# PS2Kbd.net
KiCad netlist of a schematic drawn in EAGLE
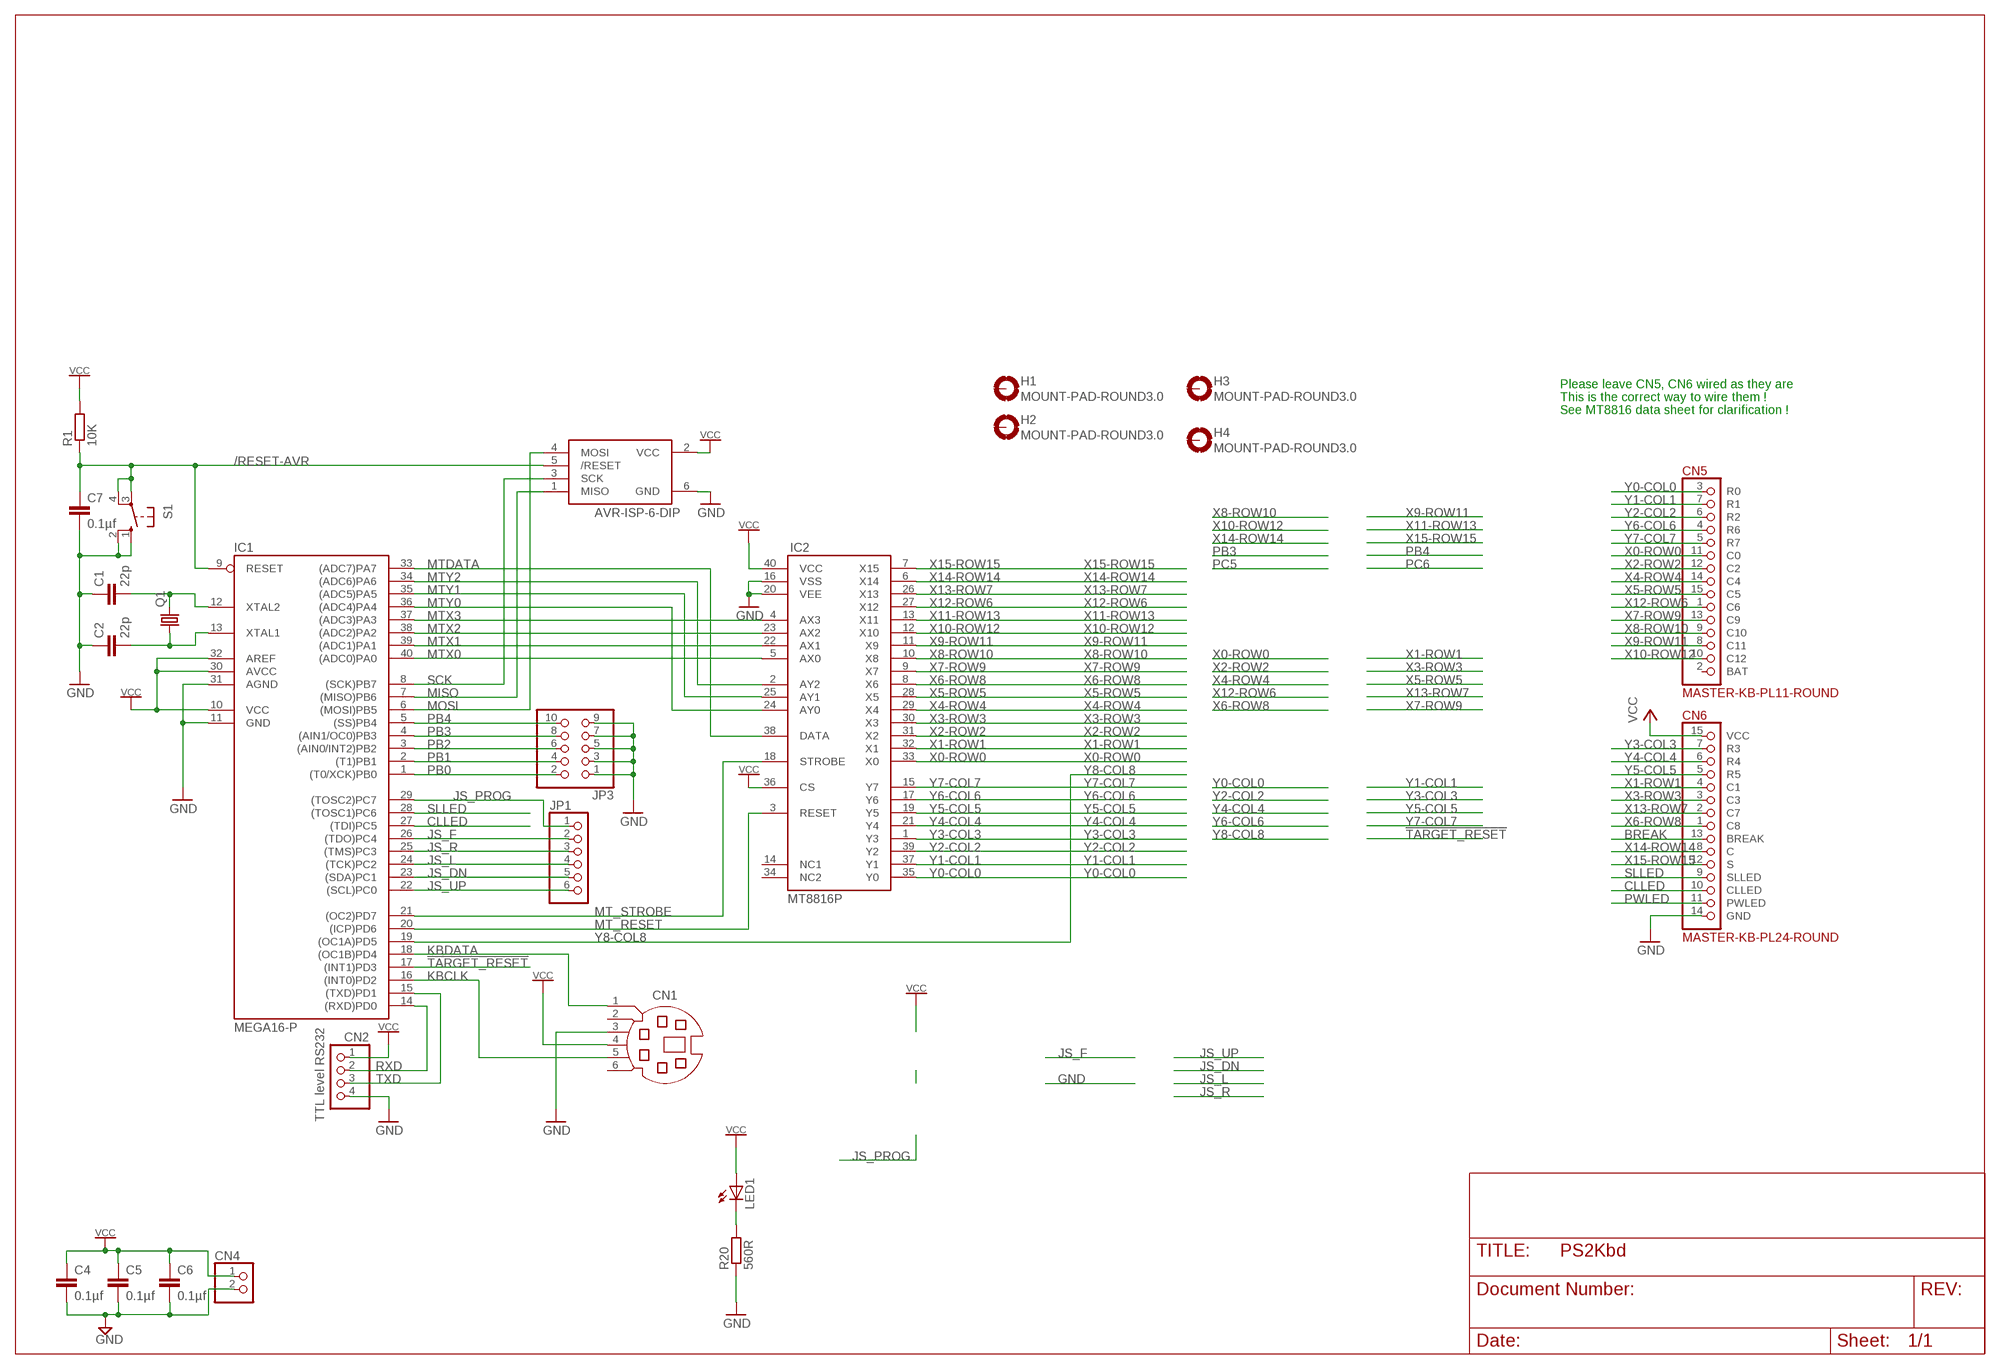
[diagram p0: schematic, sheet 1]

(export (version "E")
  (design (tool "Eeschema 10.0.6"))
  (components
    (comp (ref "C1")
      (value "22p")
      (footprint "eagle-import:C025-025X050")
      (libsource (lib "eagle-import") (part "C-EU025-025X050"))
    )
    (comp (ref "C2")
      (value "22p")
      (footprint "eagle-import:C025-025X050")
      (libsource (lib "eagle-import") (part "C-EU025-025X050"))
    )
    (comp (ref "C4")
      (value "0.1µf")
      (footprint "eagle-import:C025-025X050")
      (libsource (lib "eagle-import") (part "C-EU025-025X050"))
    )
    (comp (ref "C5")
      (value "0.1µf")
      (footprint "eagle-import:C025-025X050")
      (libsource (lib "eagle-import") (part "C-EU025-025X050"))
    )
    (comp (ref "C6")
      (value "0.1µf")
      (footprint "eagle-import:C025-025X050")
      (libsource (lib "eagle-import") (part "C-EU025-025X050"))
    )
    (comp (ref "C7")
      (value "0.1µf")
      (footprint "eagle-import:C025-025X050")
      (libsource (lib "eagle-import") (part "C-EU025-025X050"))
    )
    (comp (ref "CN1")
      (value "MD06SS")
      (footprint "eagle-import:MDIN06SS")
      (libsource (lib "eagle-import") (part "MD06SS"))
    )
    (comp (ref "CN2")
      (value "PINHD-1X4")
      (footprint "eagle-import:1X04")
      (libsource (lib "eagle-import") (part "PINHD-1X4"))
    )
    (comp (ref "CN3")
      (value "AVR-ISP-6-DIP")
      (footprint "eagle-import:2X3")
      (libsource (lib "eagle-import") (part "AVR-ISP-6-DIP"))
    )
    (comp (ref "CN4")
      (value "PINHD-1X2")
      (footprint "eagle-import:1X02")
      (libsource (lib "eagle-import") (part "PINHD-1X2"))
    )
    (comp (ref "CN5")
      (value "MASTER-KB-PL11-ROUND")
      (footprint "eagle-import:1X15-ROUND")
      (libsource (lib "eagle-import") (part "MASTER-KB-PL11-ROUND"))
    )
    (comp (ref "CN6")
      (value "MASTER-KB-PL24-ROUND")
      (footprint "eagle-import:1X15-ROUND")
      (libsource (lib "eagle-import") (part "MASTER-KB-PL24-ROUND"))
    )
    (comp (ref "H1")
      (value "MOUNT-PAD-ROUND3.0")
      (footprint "eagle-import:3,0-PAD")
      (libsource (lib "eagle-import") (part "MOUNT-PAD-ROUND3.0"))
    )
    (comp (ref "H2")
      (value "MOUNT-PAD-ROUND3.0")
      (footprint "eagle-import:3,0-PAD")
      (libsource (lib "eagle-import") (part "MOUNT-PAD-ROUND3.0"))
    )
    (comp (ref "H3")
      (value "MOUNT-PAD-ROUND3.0")
      (footprint "eagle-import:3,0-PAD")
      (libsource (lib "eagle-import") (part "MOUNT-PAD-ROUND3.0"))
    )
    (comp (ref "H4")
      (value "MOUNT-PAD-ROUND3.0")
      (footprint "eagle-import:3,0-PAD")
      (libsource (lib "eagle-import") (part "MOUNT-PAD-ROUND3.0"))
    )
    (comp (ref "IC1")
      (value "MEGA16-P")
      (footprint "eagle-import:DIL40")
      (libsource (lib "eagle-import") (part "MEGA16-P"))
    )
    (comp (ref "IC2")
      (value "MT8816P")
      (footprint "eagle-import:DIL40")
      (libsource (lib "eagle-import") (part "MT8816P"))
    )
    (comp (ref "JP1")
      (value "PINHD-1X6")
      (footprint "eagle-import:1X06")
      (libsource (lib "eagle-import") (part "PINHD-1X6"))
    )
    (comp (ref "JP3")
      (value "PINHD-2X5")
      (footprint "eagle-import:2X05")
      (libsource (lib "eagle-import") (part "PINHD-2X5"))
    )
    (comp (ref "LED1")
      (value "LED3MM")
      (footprint "eagle-import:LED3MM")
      (libsource (lib "eagle-import") (part "LED3MM"))
    )
    (comp (ref "Q1")
      (value "CRYSTALHC49S")
      (footprint "eagle-import:HC49_S")
      (libsource (lib "eagle-import") (part "CRYSTALHC49S"))
    )
    (comp (ref "R1")
      (value "10K")
      (footprint "eagle-import:0207_10")
      (libsource (lib "eagle-import") (part "R-EU_0207/10"))
    )
    (comp (ref "R20")
      (value "560R")
      (footprint "eagle-import:0207_10")
      (libsource (lib "eagle-import") (part "R-EU_0207/10"))
    )
    (comp (ref "S1")
      (value "10-XX")
      (footprint "eagle-import:B3F-10XX")
      (fields (field (name "MPN") "B3F-1000"))
      (libsource (lib "eagle-import") (part "10-XX"))
    )
  )
  (nets
    (net (code "1") (name "/BREAK") (class "Default")
      (node (ref "CN6") (pin "13") (pinfunction "BREAK_13") (pintype "passive"))
    )
    (net (code "2") (name "/CLLED") (class "Default")
      (node (ref "CN6") (pin "10") (pinfunction "CLLED_10") (pintype "passive"))
      (node (ref "IC1") (pin "27") (pinfunction "(TDI)PC5_27") (pintype "bidirectional"))
    )
    (net (code "3") (name "/JS_DN") (class "Default")
      (node (ref "IC1") (pin "23") (pinfunction "(SDA)PC1_23") (pintype "bidirectional"))
      (node (ref "JP1") (pin "5") (pinfunction "5_5") (pintype "passive"))
    )
    (net (code "4") (name "/JS_F") (class "Default")
      (node (ref "IC1") (pin "26") (pinfunction "(TDO)PC4_26") (pintype "bidirectional"))
      (node (ref "JP1") (pin "2") (pinfunction "2_2") (pintype "passive"))
    )
    (net (code "5") (name "/JS_L") (class "Default")
      (node (ref "IC1") (pin "24") (pinfunction "(TCK)PC2_24") (pintype "bidirectional"))
      (node (ref "JP1") (pin "4") (pinfunction "4_4") (pintype "passive"))
    )
    (net (code "6") (name "/JS_PROG") (class "Default")
      (node (ref "IC1") (pin "29") (pinfunction "(TOSC2)PC7_29") (pintype "bidirectional"))
      (node (ref "JP1") (pin "1") (pinfunction "1_1") (pintype "passive"))
    )
    (net (code "7") (name "/JS_R") (class "Default")
      (node (ref "IC1") (pin "25") (pinfunction "(TMS)PC3_25") (pintype "bidirectional"))
      (node (ref "JP1") (pin "3") (pinfunction "3_3") (pintype "passive"))
    )
    (net (code "8") (name "/JS_UP") (class "Default")
      (node (ref "IC1") (pin "22") (pinfunction "(SCL)PC0_22") (pintype "bidirectional"))
      (node (ref "JP1") (pin "6") (pinfunction "6_6") (pintype "passive"))
    )
    (net (code "9") (name "/KBCLK") (class "Default")
      (node (ref "CN1") (pin "5") (pinfunction "5_5") (pintype "passive"))
      (node (ref "IC1") (pin "16") (pinfunction "(INT0)PD2_16") (pintype "bidirectional"))
    )
    (net (code "10") (name "/KBDATA") (class "Default")
      (node (ref "CN1") (pin "1") (pinfunction "1_1") (pintype "passive"))
      (node (ref "IC1") (pin "18") (pinfunction "(OC1B)PD4_18") (pintype "bidirectional"))
    )
    (net (code "11") (name "/MISO") (class "Default")
      (node (ref "CN3") (pin "1") (pinfunction "MISO_1") (pintype "bidirectional"))
      (node (ref "IC1") (pin "7") (pinfunction "(MISO)PB6_7") (pintype "bidirectional"))
    )
    (net (code "12") (name "/MOSI") (class "Default")
      (node (ref "CN3") (pin "4") (pinfunction "MOSI_4") (pintype "bidirectional"))
      (node (ref "IC1") (pin "6") (pinfunction "(MOSI)PB5_6") (pintype "bidirectional"))
    )
    (net (code "13") (name "/MTDATA") (class "Default")
      (node (ref "IC1") (pin "33") (pinfunction "(ADC7)PA7_33") (pintype "bidirectional"))
      (node (ref "IC2") (pin "38") (pinfunction "DATA_38") (pintype "input"))
    )
    (net (code "14") (name "/MTX0") (class "Default")
      (node (ref "IC1") (pin "40") (pinfunction "(ADC0)PA0_40") (pintype "bidirectional"))
      (node (ref "IC2") (pin "5") (pinfunction "AX0_5") (pintype "input"))
    )
    (net (code "15") (name "/MTX1") (class "Default")
      (node (ref "IC1") (pin "39") (pinfunction "(ADC1)PA1_39") (pintype "bidirectional"))
      (node (ref "IC2") (pin "22") (pinfunction "AX1_22") (pintype "input"))
    )
    (net (code "16") (name "/MTX2") (class "Default")
      (node (ref "IC1") (pin "38") (pinfunction "(ADC2)PA2_38") (pintype "bidirectional"))
      (node (ref "IC2") (pin "23") (pinfunction "AX2_23") (pintype "input"))
    )
    (net (code "17") (name "/MTX3") (class "Default")
      (node (ref "IC1") (pin "37") (pinfunction "(ADC3)PA3_37") (pintype "bidirectional"))
      (node (ref "IC2") (pin "4") (pinfunction "AX3_4") (pintype "input"))
    )
    (net (code "18") (name "/MTY0") (class "Default")
      (node (ref "IC1") (pin "36") (pinfunction "(ADC4)PA4_36") (pintype "bidirectional"))
      (node (ref "IC2") (pin "24") (pinfunction "AY0_24") (pintype "input"))
    )
    (net (code "19") (name "/MTY1") (class "Default")
      (node (ref "IC1") (pin "35") (pinfunction "(ADC5)PA5_35") (pintype "bidirectional"))
      (node (ref "IC2") (pin "25") (pinfunction "AY1_25") (pintype "input"))
    )
    (net (code "20") (name "/MTY2") (class "Default")
      (node (ref "IC1") (pin "34") (pinfunction "(ADC6)PA6_34") (pintype "bidirectional"))
      (node (ref "IC2") (pin "2") (pinfunction "AY2_2") (pintype "input"))
    )
    (net (code "21") (name "/MT_RESET") (class "Default")
      (node (ref "IC1") (pin "20") (pinfunction "(ICP)PD6_20") (pintype "bidirectional"))
      (node (ref "IC2") (pin "3") (pinfunction "RESET_3") (pintype "input"))
    )
    (net (code "22") (name "/MT_STROBE") (class "Default")
      (node (ref "IC1") (pin "21") (pinfunction "(OC2)PD7_21") (pintype "bidirectional"))
      (node (ref "IC2") (pin "18") (pinfunction "STROBE_18") (pintype "input"))
    )
    (net (code "23") (name "/PB0") (class "Default")
      (node (ref "IC1") (pin "1") (pinfunction "(T0/XCK)PB0_1") (pintype "bidirectional"))
      (node (ref "JP3") (pin "2") (pinfunction "2_2") (pintype "passive"))
    )
    (net (code "24") (name "/PB1") (class "Default")
      (node (ref "IC1") (pin "2") (pinfunction "(T1)PB1_2") (pintype "bidirectional"))
      (node (ref "JP3") (pin "4") (pinfunction "4_4") (pintype "passive"))
    )
    (net (code "25") (name "/PB2") (class "Default")
      (node (ref "IC1") (pin "3") (pinfunction "(AIN0/INT2)PB2_3") (pintype "bidirectional"))
      (node (ref "JP3") (pin "6") (pinfunction "6_6") (pintype "passive"))
    )
    (net (code "26") (name "/PB3") (class "Default")
      (node (ref "IC1") (pin "4") (pinfunction "(AIN1/OC0)PB3_4") (pintype "bidirectional"))
      (node (ref "JP3") (pin "8") (pinfunction "8_8") (pintype "passive"))
    )
    (net (code "27") (name "/PB4") (class "Default")
      (node (ref "IC1") (pin "5") (pinfunction "(SS)PB4_5") (pintype "bidirectional"))
      (node (ref "JP3") (pin "10") (pinfunction "10_10") (pintype "passive"))
    )
    (net (code "30") (name "/PWLED") (class "Default")
      (node (ref "CN6") (pin "11") (pinfunction "PWLED_11") (pintype "passive"))
    )
    (net (code "31") (name "/RXD") (class "Default")
      (node (ref "CN2") (pin "2") (pinfunction "2_2") (pintype "passive"))
      (node (ref "IC1") (pin "14") (pinfunction "(RXD)PD0_14") (pintype "bidirectional"))
    )
    (net (code "32") (name "/SCK") (class "Default")
      (node (ref "CN3") (pin "3") (pinfunction "SCK_3") (pintype "bidirectional"))
      (node (ref "IC1") (pin "8") (pinfunction "(SCK)PB7_8") (pintype "bidirectional"))
    )
    (net (code "33") (name "/SLLED") (class "Default")
      (node (ref "CN6") (pin "9") (pinfunction "SLLED_9") (pintype "passive"))
      (node (ref "IC1") (pin "28") (pinfunction "(TOSC1)PC6_28") (pintype "bidirectional"))
    )
    (net (code "34") (name "/TXD") (class "Default")
      (node (ref "CN2") (pin "3") (pinfunction "3_3") (pintype "passive"))
      (node (ref "IC1") (pin "15") (pinfunction "(TXD)PD1_15") (pintype "bidirectional"))
    )
    (net (code "35") (name "/X0-ROW0") (class "Default")
      (node (ref "CN5") (pin "11") (pinfunction "C0_11") (pintype "passive"))
      (node (ref "IC2") (pin "33") (pinfunction "X0_33") (pintype "bidirectional"))
    )
    (net (code "36") (name "/X1-ROW1") (class "Default")
      (node (ref "CN6") (pin "4") (pinfunction "C1_4") (pintype "passive"))
      (node (ref "IC2") (pin "32") (pinfunction "X1_32") (pintype "bidirectional"))
    )
    (net (code "37") (name "/X2-ROW2") (class "Default")
      (node (ref "CN5") (pin "12") (pinfunction "C2_12") (pintype "passive"))
      (node (ref "IC2") (pin "31") (pinfunction "X2_31") (pintype "bidirectional"))
    )
    (net (code "38") (name "/X3-ROW3") (class "Default")
      (node (ref "CN6") (pin "3") (pinfunction "C3_3") (pintype "passive"))
      (node (ref "IC2") (pin "30") (pinfunction "X3_30") (pintype "bidirectional"))
    )
    (net (code "39") (name "/X4-ROW4") (class "Default")
      (node (ref "CN5") (pin "14") (pinfunction "C4_14") (pintype "passive"))
      (node (ref "IC2") (pin "29") (pinfunction "X4_29") (pintype "bidirectional"))
    )
    (net (code "40") (name "/X5-ROW5") (class "Default")
      (node (ref "CN5") (pin "15") (pinfunction "C5_15") (pintype "passive"))
      (node (ref "IC2") (pin "28") (pinfunction "X5_28") (pintype "bidirectional"))
    )
    (net (code "41") (name "/X6-ROW8") (class "Default")
      (node (ref "CN6") (pin "1") (pinfunction "C8_1") (pintype "passive"))
      (node (ref "IC2") (pin "8") (pinfunction "X6_8") (pintype "bidirectional"))
    )
    (net (code "42") (name "/X7-ROW9") (class "Default")
      (node (ref "CN5") (pin "13") (pinfunction "C9_13") (pintype "passive"))
      (node (ref "IC2") (pin "9") (pinfunction "X7_9") (pintype "bidirectional"))
    )
    (net (code "43") (name "/X8-ROW10") (class "Default")
      (node (ref "CN5") (pin "9") (pinfunction "C10_9") (pintype "passive"))
      (node (ref "IC2") (pin "10") (pinfunction "X8_10") (pintype "bidirectional"))
    )
    (net (code "44") (name "/X9-ROW11") (class "Default")
      (node (ref "CN5") (pin "8") (pinfunction "C11_8") (pintype "passive"))
      (node (ref "IC2") (pin "11") (pinfunction "X9_11") (pintype "bidirectional"))
    )
    (net (code "45") (name "/X10-ROW12") (class "Default")
      (node (ref "CN5") (pin "10") (pinfunction "C12_10") (pintype "passive"))
      (node (ref "IC2") (pin "12") (pinfunction "X10_12") (pintype "bidirectional"))
    )
    (net (code "46") (name "/X11-ROW13") (class "Default")
      (node (ref "IC2") (pin "13") (pinfunction "X11_13") (pintype "bidirectional"))
    )
    (net (code "47") (name "/X12-ROW6") (class "Default")
      (node (ref "CN5") (pin "1") (pinfunction "C6_1") (pintype "passive"))
      (node (ref "IC2") (pin "27") (pinfunction "X12_27") (pintype "bidirectional"))
    )
    (net (code "48") (name "/X13-ROW7") (class "Default")
      (node (ref "CN6") (pin "2") (pinfunction "C7_2") (pintype "passive"))
      (node (ref "IC2") (pin "26") (pinfunction "X13_26") (pintype "bidirectional"))
    )
    (net (code "49") (name "/X14-ROW14") (class "Default")
      (node (ref "CN6") (pin "8") (pinfunction "C_8") (pintype "passive"))
      (node (ref "IC2") (pin "6") (pinfunction "X14_6") (pintype "bidirectional"))
    )
    (net (code "50") (name "/X15-ROW15") (class "Default")
      (node (ref "CN6") (pin "12") (pinfunction "S_12") (pintype "passive"))
      (node (ref "IC2") (pin "7") (pinfunction "X15_7") (pintype "bidirectional"))
    )
    (net (code "51") (name "/Y0-COL0") (class "Default")
      (node (ref "CN5") (pin "3") (pinfunction "R0_3") (pintype "passive"))
      (node (ref "IC2") (pin "35") (pinfunction "Y0_35") (pintype "bidirectional"))
    )
    (net (code "52") (name "/Y1-COL1") (class "Default")
      (node (ref "CN5") (pin "7") (pinfunction "R1_7") (pintype "passive"))
      (node (ref "IC2") (pin "37") (pinfunction "Y1_37") (pintype "bidirectional"))
    )
    (net (code "53") (name "/Y2-COL2") (class "Default")
      (node (ref "CN5") (pin "6") (pinfunction "R2_6") (pintype "passive"))
      (node (ref "IC2") (pin "39") (pinfunction "Y2_39") (pintype "bidirectional"))
    )
    (net (code "54") (name "/Y3-COL3") (class "Default")
      (node (ref "CN6") (pin "7") (pinfunction "R3_7") (pintype "passive"))
      (node (ref "IC2") (pin "1") (pinfunction "Y3_1") (pintype "bidirectional"))
    )
    (net (code "55") (name "/Y4-COL4") (class "Default")
      (node (ref "CN6") (pin "6") (pinfunction "R4_6") (pintype "passive"))
      (node (ref "IC2") (pin "21") (pinfunction "Y4_21") (pintype "bidirectional"))
    )
    (net (code "56") (name "/Y5-COL5") (class "Default")
      (node (ref "CN6") (pin "5") (pinfunction "R5_5") (pintype "passive"))
      (node (ref "IC2") (pin "19") (pinfunction "Y5_19") (pintype "bidirectional"))
    )
    (net (code "57") (name "/Y6-COL6") (class "Default")
      (node (ref "CN5") (pin "4") (pinfunction "R6_4") (pintype "passive"))
      (node (ref "IC2") (pin "17") (pinfunction "Y6_17") (pintype "bidirectional"))
    )
    (net (code "58") (name "/Y7-COL7") (class "Default")
      (node (ref "CN5") (pin "5") (pinfunction "R7_5") (pintype "passive"))
      (node (ref "IC2") (pin "15") (pinfunction "Y7_15") (pintype "bidirectional"))
    )
    (net (code "59") (name "/Y8-COL8") (class "Default")
      (node (ref "IC1") (pin "19") (pinfunction "(OC1A)PD5_19") (pintype "bidirectional"))
    )
    (net (code "60") (name "/{slash}RESET-AVR") (class "Default")
      (node (ref "C7") (pin "1") (pinfunction "1_1") (pintype "passive"))
      (node (ref "CN3") (pin "5") (pinfunction "/RESET_5") (pintype "bidirectional"))
      (node (ref "IC1") (pin "9") (pinfunction "RESET_9") (pintype "input"))
      (node (ref "R1") (pin "1") (pinfunction "1_1") (pintype "passive"))
      (node (ref "S1") (pin "3") (pinfunction "P_3") (pintype "passive"))
      (node (ref "S1") (pin "4") (pinfunction "P1_4") (pintype "passive"))
    )
    (net (code "61") (name "/~{TARGET_RESET}") (class "Default")
      (node (ref "IC1") (pin "17") (pinfunction "(INT1)PD3_17") (pintype "bidirectional"))
    )
    (net (code "62") (name "GND") (class "Default")
      (node (ref "C1") (pin "1") (pinfunction "1_1") (pintype "passive"))
      (node (ref "C2") (pin "1") (pinfunction "1_1") (pintype "passive"))
      (node (ref "C4") (pin "2") (pinfunction "2_2") (pintype "passive"))
      (node (ref "C5") (pin "2") (pinfunction "2_2") (pintype "passive"))
      (node (ref "C6") (pin "2") (pinfunction "2_2") (pintype "passive"))
      (node (ref "C7") (pin "2") (pinfunction "2_2") (pintype "passive"))
      (node (ref "CN1") (pin "3") (pinfunction "3_3") (pintype "passive"))
      (node (ref "CN2") (pin "4") (pinfunction "4_4") (pintype "passive"))
      (node (ref "CN3") (pin "6") (pinfunction "GND_6") (pintype "power_in"))
      (node (ref "CN4") (pin "2") (pinfunction "2_2") (pintype "passive"))
      (node (ref "CN6") (pin "14") (pinfunction "GND_14") (pintype "passive"))
      (node (ref "IC1") (pin "11") (pinfunction "GND_11") (pintype "power_in"))
      (node (ref "IC1") (pin "31") (pinfunction "AGND_31") (pintype "power_in"))
      (node (ref "IC2") (pin "16") (pinfunction "VSS_16") (pintype "power_in"))
      (node (ref "IC2") (pin "20") (pinfunction "VEE_20") (pintype "power_in"))
      (node (ref "JP3") (pin "1") (pinfunction "1_1") (pintype "passive"))
      (node (ref "JP3") (pin "3") (pinfunction "3_3") (pintype "passive"))
      (node (ref "JP3") (pin "5") (pinfunction "5_5") (pintype "passive"))
      (node (ref "JP3") (pin "7") (pinfunction "7_7") (pintype "passive"))
      (node (ref "JP3") (pin "9") (pinfunction "9_9") (pintype "passive"))
      (node (ref "R20") (pin "1") (pinfunction "1_1") (pintype "passive"))
      (node (ref "S1") (pin "1") (pinfunction "S_1") (pintype "passive"))
      (node (ref "S1") (pin "2") (pinfunction "S1_2") (pintype "passive"))
    )
    (net (code "63") (name "Net-(IC1-XTAL1)") (class "Default")
      (node (ref "C2") (pin "2") (pinfunction "2_2") (pintype "passive"))
      (node (ref "IC1") (pin "13") (pinfunction "XTAL1_13") (pintype "bidirectional"))
      (node (ref "Q1") (pin "1") (pinfunction "1_1") (pintype "passive"))
    )
    (net (code "64") (name "Net-(IC1-XTAL2)") (class "Default")
      (node (ref "C1") (pin "2") (pinfunction "2_2") (pintype "passive"))
      (node (ref "IC1") (pin "12") (pinfunction "XTAL2_12") (pintype "bidirectional"))
      (node (ref "Q1") (pin "2") (pinfunction "2_2") (pintype "passive"))
    )
    (net (code "65") (name "Net-(LED1-C)") (class "Default")
      (node (ref "LED1") (pin "K") (pinfunction "C_K") (pintype "passive"))
      (node (ref "R20") (pin "2") (pinfunction "2_2") (pintype "passive"))
    )
    (net (code "66") (name "VCC") (class "Default")
      (node (ref "C4") (pin "1") (pinfunction "1_1") (pintype "passive"))
      (node (ref "C5") (pin "1") (pinfunction "1_1") (pintype "passive"))
      (node (ref "C6") (pin "1") (pinfunction "1_1") (pintype "passive"))
      (node (ref "CN1") (pin "4") (pinfunction "4_4") (pintype "passive"))
      (node (ref "CN2") (pin "1") (pinfunction "1_1") (pintype "passive"))
      (node (ref "CN3") (pin "2") (pinfunction "VCC_2") (pintype "power_in"))
      (node (ref "CN4") (pin "1") (pinfunction "1_1") (pintype "passive"))
      (node (ref "CN6") (pin "15") (pinfunction "VCC_15") (pintype "passive"))
      (node (ref "IC1") (pin "10") (pinfunction "VCC_10") (pintype "power_in"))
      (node (ref "IC1") (pin "30") (pinfunction "AVCC_30") (pintype "power_in"))
      (node (ref "IC1") (pin "32") (pinfunction "AREF_32") (pintype "power_in"))
      (node (ref "IC2") (pin "36") (pinfunction "CS_36") (pintype "input"))
      (node (ref "IC2") (pin "40") (pinfunction "VCC_40") (pintype "power_in"))
      (node (ref "LED1") (pin "A") (pinfunction "A_A") (pintype "passive"))
      (node (ref "R1") (pin "2") (pinfunction "2_2") (pintype "passive"))
    )
    (net (code "67") (name "unconnected-(CN1-Pad2)") (class "Default")
      (node (ref "CN1") (pin "2") (pinfunction "2_2") (pintype "passive"))
    )
    (net (code "68") (name "unconnected-(CN1-Pad6)") (class "Default")
      (node (ref "CN1") (pin "6") (pinfunction "6_6") (pintype "passive"))
    )
    (net (code "69") (name "unconnected-(CN5-BAT-Pad2)") (class "Default")
      (node (ref "CN5") (pin "2") (pinfunction "BAT_2") (pintype "passive"))
    )
    (net (code "70") (name "unconnected-(H1-MOUNT-PadB3,0)") (class "Default")
      (node (ref "H1") (pin "B3,0") (pinfunction "MOUNT_B3,0") (pintype "passive"))
    )
    (net (code "71") (name "unconnected-(H2-MOUNT-PadB3,0)") (class "Default")
      (node (ref "H2") (pin "B3,0") (pinfunction "MOUNT_B3,0") (pintype "passive"))
    )
    (net (code "72") (name "unconnected-(H3-MOUNT-PadB3,0)") (class "Default")
      (node (ref "H3") (pin "B3,0") (pinfunction "MOUNT_B3,0") (pintype "passive"))
    )
    (net (code "73") (name "unconnected-(H4-MOUNT-PadB3,0)") (class "Default")
      (node (ref "H4") (pin "B3,0") (pinfunction "MOUNT_B3,0") (pintype "passive"))
    )
    (net (code "74") (name "unconnected-(IC2-NC1-Pad14)") (class "Default")
      (node (ref "IC2") (pin "14") (pinfunction "NC1_14") (pintype "no_connect"))
    )
    (net (code "75") (name "unconnected-(IC2-NC2-Pad34)") (class "Default")
      (node (ref "IC2") (pin "34") (pinfunction "NC2_34") (pintype "no_connect"))
    )
  )
)
